# SH4_-_GIMBDRIVE_CONTROLS.net
KiCad netlist of a schematic drawn in Altium Designer
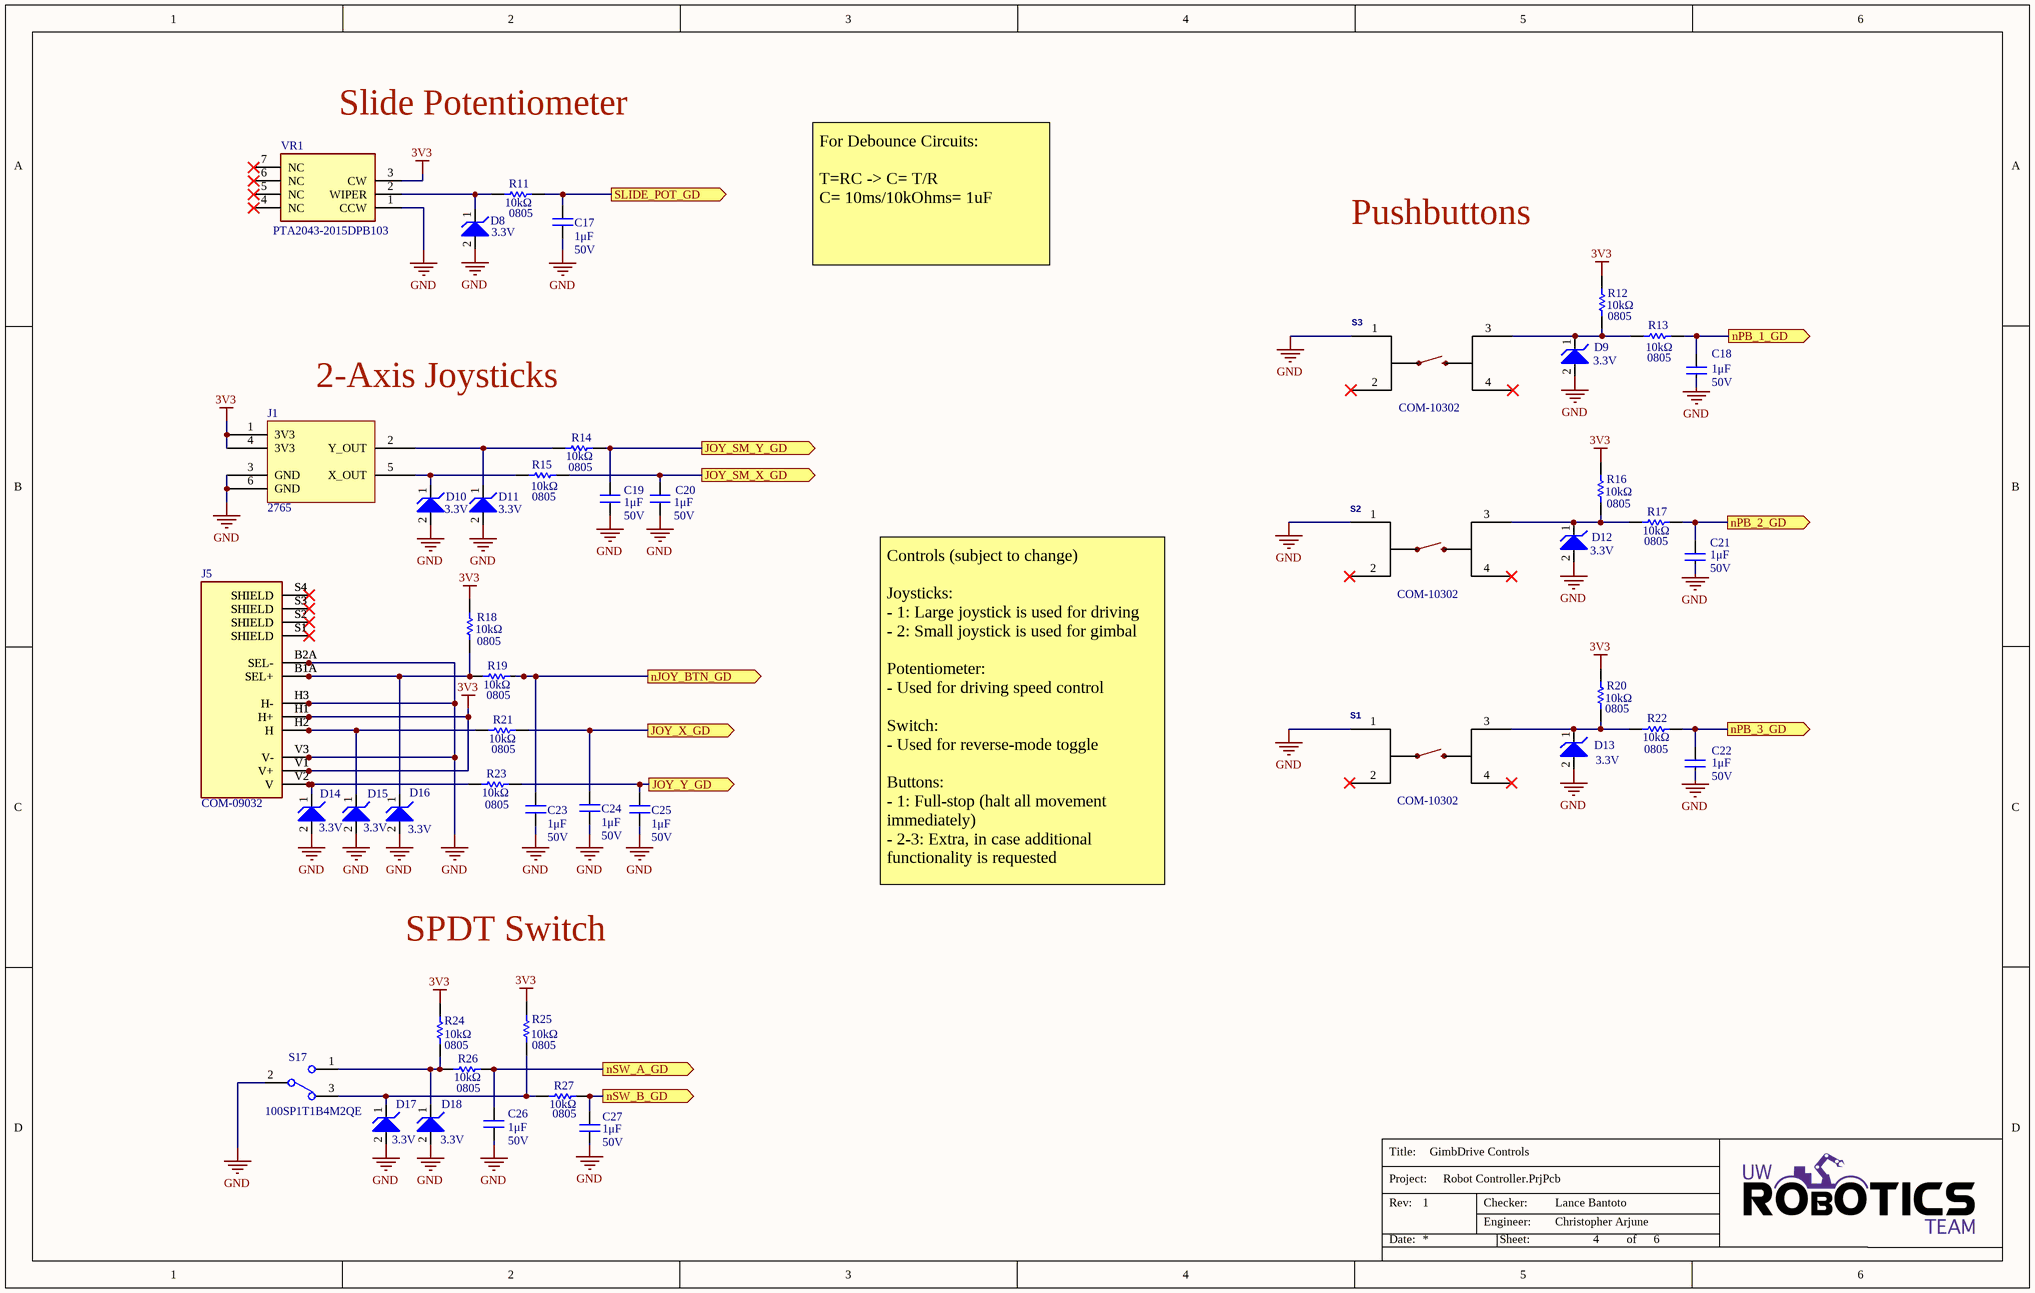
[diagram p0: SH4 - GIMBDRIVE CONTROLS.SchDoc]

(export (version "E")
  (design (tool "Eeschema 10.0.6"))
  (components
    (comp (ref "C17")
      (value "1μF")
      (footprint "CAP2012")
      (description "CAP CER 1UF 50V X7R 0805")
      (fields
        (field (name "VOLTAGE RATING") "50V")
        (field (name "LCSC PART #") "C28323")
        (field (name "Comment") "CAP_1uF_50V_0805")
      )
      (libsource (lib "UWRT_Schematic_Library_2020") (part "CAP_1uF_50V_0805"))
    )
    (comp (ref "C18")
      (value "1μF")
      (footprint "CAP2012")
      (description "CAP CER 1UF 50V X7R 0805")
      (fields
        (field (name "VOLTAGE RATING") "50V")
        (field (name "LCSC PART #") "C28323")
        (field (name "Comment") "CAP_1uF_50V_0805")
      )
      (libsource (lib "UWRT_Schematic_Library_2020") (part "CAP_1uF_50V_0805"))
    )
    (comp (ref "C19")
      (value "1μF")
      (footprint "CAP2012")
      (description "CAP CER 1UF 50V X7R 0805")
      (fields
        (field (name "VOLTAGE RATING") "50V")
        (field (name "LCSC PART #") "C28323")
        (field (name "Comment") "CAP_1uF_50V_0805")
      )
      (libsource (lib "UWRT_Schematic_Library_2020") (part "CAP_1uF_50V_0805"))
    )
    (comp (ref "C20")
      (value "1μF")
      (footprint "CAP2012")
      (description "CAP CER 1UF 50V X7R 0805")
      (fields
        (field (name "VOLTAGE RATING") "50V")
        (field (name "LCSC PART #") "C28323")
        (field (name "Comment") "CAP_1uF_50V_0805")
      )
      (libsource (lib "UWRT_Schematic_Library_2020") (part "CAP_1uF_50V_0805"))
    )
    (comp (ref "C21")
      (value "1μF")
      (footprint "CAP2012")
      (description "CAP CER 1UF 50V X7R 0805")
      (fields
        (field (name "VOLTAGE RATING") "50V")
        (field (name "LCSC PART #") "C28323")
        (field (name "Comment") "CAP_1uF_50V_0805")
      )
      (libsource (lib "UWRT_Schematic_Library_2020") (part "CAP_1uF_50V_0805"))
    )
    (comp (ref "C22")
      (value "1μF")
      (footprint "CAP2012")
      (description "CAP CER 1UF 50V X7R 0805")
      (fields
        (field (name "VOLTAGE RATING") "50V")
        (field (name "LCSC PART #") "C28323")
        (field (name "Comment") "CAP_1uF_50V_0805")
      )
      (libsource (lib "UWRT_Schematic_Library_2020") (part "CAP_1uF_50V_0805"))
    )
    (comp (ref "C23")
      (value "1μF")
      (footprint "CAP2012")
      (description "CAP CER 1UF 50V X7R 0805")
      (fields
        (field (name "VOLTAGE RATING") "50V")
        (field (name "LCSC PART #") "C28323")
        (field (name "Comment") "CAP_1uF_50V_0805")
      )
      (libsource (lib "UWRT_Schematic_Library_2020") (part "CAP_1uF_50V_0805"))
    )
    (comp (ref "C24")
      (value "1μF")
      (footprint "CAP2012")
      (description "CAP CER 1UF 50V X7R 0805")
      (fields
        (field (name "VOLTAGE RATING") "50V")
        (field (name "LCSC PART #") "C28323")
        (field (name "Comment") "CAP_1uF_50V_0805")
      )
      (libsource (lib "UWRT_Schematic_Library_2020") (part "CAP_1uF_50V_0805"))
    )
    (comp (ref "C25")
      (value "1μF")
      (footprint "CAP2012")
      (description "CAP CER 1UF 50V X7R 0805")
      (fields
        (field (name "VOLTAGE RATING") "50V")
        (field (name "LCSC PART #") "C28323")
        (field (name "Comment") "CAP_1uF_50V_0805")
      )
      (libsource (lib "UWRT_Schematic_Library_2020") (part "CAP_1uF_50V_0805"))
    )
    (comp (ref "C26")
      (value "1μF")
      (footprint "CAP2012")
      (description "CAP CER 1UF 50V X7R 0805")
      (fields
        (field (name "VOLTAGE RATING") "50V")
        (field (name "LCSC PART #") "C28323")
        (field (name "Comment") "CAP_1uF_50V_0805")
      )
      (libsource (lib "UWRT_Schematic_Library_2020") (part "CAP_1uF_50V_0805"))
    )
    (comp (ref "C27")
      (value "1μF")
      (footprint "CAP2012")
      (description "CAP CER 1UF 50V X7R 0805")
      (fields
        (field (name "VOLTAGE RATING") "50V")
        (field (name "LCSC PART #") "C28323")
        (field (name "Comment") "CAP_1uF_50V_0805")
      )
      (libsource (lib "UWRT_Schematic_Library_2020") (part "CAP_1uF_50V_0805"))
    )
    (comp (ref "D8")
      (value "TVS_DIODE_UNIDIR_3.3V")
      (description "TVS DIODE 3.3V 14.1V SOD523")
      (fields (field (name "LCSC PART #") "C61148") (field (name "VOLTAGE - REVERSE STANDOFF (TYP)") "3.3V"))
      (libsource (lib "UWRT_Schematic_Library_2020") (part "TVS_DIODE_UNIDIR_3.3V"))
    )
    (comp (ref "D9")
      (value "TVS_DIODE_UNIDIR_3.3V")
      (description "TVS DIODE 3.3V 14.1V SOD523")
      (fields (field (name "LCSC PART #") "C61148") (field (name "VOLTAGE - REVERSE STANDOFF (TYP)") "3.3V"))
      (libsource (lib "UWRT_Schematic_Library_2020") (part "TVS_DIODE_UNIDIR_3.3V"))
    )
    (comp (ref "D10")
      (value "TVS_DIODE_UNIDIR_3.3V")
      (description "TVS DIODE 3.3V 14.1V SOD523")
      (fields (field (name "LCSC PART #") "C61148") (field (name "VOLTAGE - REVERSE STANDOFF (TYP)") "3.3V"))
      (libsource (lib "UWRT_Schematic_Library_2020") (part "TVS_DIODE_UNIDIR_3.3V"))
    )
    (comp (ref "D11")
      (value "TVS_DIODE_UNIDIR_3.3V")
      (description "TVS DIODE 3.3V 14.1V SOD523")
      (fields (field (name "LCSC PART #") "C61148") (field (name "VOLTAGE - REVERSE STANDOFF (TYP)") "3.3V"))
      (libsource (lib "UWRT_Schematic_Library_2020") (part "TVS_DIODE_UNIDIR_3.3V"))
    )
    (comp (ref "D12")
      (value "TVS_DIODE_UNIDIR_3.3V")
      (description "TVS DIODE 3.3V 14.1V SOD523")
      (fields (field (name "LCSC PART #") "C61148") (field (name "VOLTAGE - REVERSE STANDOFF (TYP)") "3.3V"))
      (libsource (lib "UWRT_Schematic_Library_2020") (part "TVS_DIODE_UNIDIR_3.3V"))
    )
    (comp (ref "D13")
      (value "TVS_DIODE_UNIDIR_3.3V")
      (description "TVS DIODE 3.3V 14.1V SOD523")
      (fields (field (name "LCSC PART #") "C61148") (field (name "VOLTAGE - REVERSE STANDOFF (TYP)") "3.3V"))
      (libsource (lib "UWRT_Schematic_Library_2020") (part "TVS_DIODE_UNIDIR_3.3V"))
    )
    (comp (ref "D14")
      (value "TVS_DIODE_UNIDIR_3.3V")
      (description "TVS DIODE 3.3V 14.1V SOD523")
      (fields (field (name "LCSC PART #") "C61148") (field (name "VOLTAGE - REVERSE STANDOFF (TYP)") "3.3V"))
      (libsource (lib "UWRT_Schematic_Library_2020") (part "TVS_DIODE_UNIDIR_3.3V"))
    )
    (comp (ref "D15")
      (value "TVS_DIODE_UNIDIR_3.3V")
      (description "TVS DIODE 3.3V 14.1V SOD523")
      (fields (field (name "LCSC PART #") "C61148") (field (name "VOLTAGE - REVERSE STANDOFF (TYP)") "3.3V"))
      (libsource (lib "UWRT_Schematic_Library_2020") (part "TVS_DIODE_UNIDIR_3.3V"))
    )
    (comp (ref "D16")
      (value "TVS_DIODE_UNIDIR_3.3V")
      (description "TVS DIODE 3.3V 14.1V SOD523")
      (fields (field (name "LCSC PART #") "C61148") (field (name "VOLTAGE - REVERSE STANDOFF (TYP)") "3.3V"))
      (libsource (lib "UWRT_Schematic_Library_2020") (part "TVS_DIODE_UNIDIR_3.3V"))
    )
    (comp (ref "D17")
      (value "TVS_DIODE_UNIDIR_3.3V")
      (description "TVS DIODE 3.3V 14.1V SOD523")
      (fields (field (name "LCSC PART #") "C61148") (field (name "VOLTAGE - REVERSE STANDOFF (TYP)") "3.3V"))
      (libsource (lib "UWRT_Schematic_Library_2020") (part "TVS_DIODE_UNIDIR_3.3V"))
    )
    (comp (ref "D18")
      (value "TVS_DIODE_UNIDIR_3.3V")
      (description "TVS DIODE 3.3V 14.1V SOD523")
      (fields (field (name "LCSC PART #") "C61148") (field (name "VOLTAGE - REVERSE STANDOFF (TYP)") "3.3V"))
      (libsource (lib "UWRT_Schematic_Library_2020") (part "TVS_DIODE_UNIDIR_3.3V"))
    )
    (comp (ref "J1")
      (value "2_AXIS_JOYSTICK_SMALL")
      (footprint "2_AXIS_JOYSTICK_SMALL")
      (description "JOYSTICK 10K OHM 2 AXIS TH")
      (fields (field (name "MANUFACTURER PART NUMBER 1") "2765"))
      (libsource (lib "UWRT_Schematic_Library_2020") (part "2_AXIS_JOYSTICK_SMALL"))
    )
    (comp (ref "J5")
      (value "2_AXIS_JOYSTICK")
      (footprint "2_AXIS_JOYSTICK")
      (description "JOYSTICK 10K OHM 2 AXIS TH")
      (fields (field (name "MANUFACTURER PART NUMBER 1") "COM-09032"))
      (libsource (lib "UWRT_Schematic_Library_2020") (part "2_AXIS_JOYSTICK"))
    )
    (comp (ref "R11")
      (value "10kΩ")
      (footprint "RESC0805")
      (description "RES 10K OHM 5% 1/8W 0805")
      (fields
        (field (name "LCSC PART #") "C17414")
        (field (name "PACKAGE/FOOTPRINT") "0805")
        (field (name "Comment") "RES_10kΩ_0805_5%")
      )
      (libsource (lib "UWRT_Schematic_Library_2020") (part "RES_10kΩ_0805_5%"))
    )
    (comp (ref "R12")
      (value "10kΩ")
      (footprint "RESC0805")
      (description "RES 10K OHM 5% 1/8W 0805")
      (fields
        (field (name "LCSC PART #") "C17414")
        (field (name "PACKAGE/FOOTPRINT") "0805")
        (field (name "Comment") "RES_10kΩ_0805_5%")
      )
      (libsource (lib "UWRT_Schematic_Library_2020") (part "RES_10kΩ_0805_5%"))
    )
    (comp (ref "R13")
      (value "10kΩ")
      (footprint "RESC0805")
      (description "RES 10K OHM 5% 1/8W 0805")
      (fields
        (field (name "LCSC PART #") "C17414")
        (field (name "PACKAGE/FOOTPRINT") "0805")
        (field (name "Comment") "RES_10kΩ_0805_5%")
      )
      (libsource (lib "UWRT_Schematic_Library_2020") (part "RES_10kΩ_0805_5%"))
    )
    (comp (ref "R14")
      (value "10kΩ")
      (footprint "RESC0805")
      (description "RES 10K OHM 5% 1/8W 0805")
      (fields
        (field (name "LCSC PART #") "C17414")
        (field (name "PACKAGE/FOOTPRINT") "0805")
        (field (name "Comment") "RES_10kΩ_0805_5%")
      )
      (libsource (lib "UWRT_Schematic_Library_2020") (part "RES_10kΩ_0805_5%"))
    )
    (comp (ref "R15")
      (value "10kΩ")
      (footprint "RESC0805")
      (description "RES 10K OHM 5% 1/8W 0805")
      (fields
        (field (name "LCSC PART #") "C17414")
        (field (name "PACKAGE/FOOTPRINT") "0805")
        (field (name "Comment") "RES_10kΩ_0805_5%")
      )
      (libsource (lib "UWRT_Schematic_Library_2020") (part "RES_10kΩ_0805_5%"))
    )
    (comp (ref "R16")
      (value "10kΩ")
      (footprint "RESC0805")
      (description "RES 10K OHM 5% 1/8W 0805")
      (fields
        (field (name "LCSC PART #") "C17414")
        (field (name "PACKAGE/FOOTPRINT") "0805")
        (field (name "Comment") "RES_10kΩ_0805_5%")
      )
      (libsource (lib "UWRT_Schematic_Library_2020") (part "RES_10kΩ_0805_5%"))
    )
    (comp (ref "R17")
      (value "10kΩ")
      (footprint "RESC0805")
      (description "RES 10K OHM 5% 1/8W 0805")
      (fields
        (field (name "LCSC PART #") "C17414")
        (field (name "PACKAGE/FOOTPRINT") "0805")
        (field (name "Comment") "RES_10kΩ_0805_5%")
      )
      (libsource (lib "UWRT_Schematic_Library_2020") (part "RES_10kΩ_0805_5%"))
    )
    (comp (ref "R18")
      (value "10kΩ")
      (footprint "RESC0805")
      (description "RES 10K OHM 5% 1/8W 0805")
      (fields
        (field (name "LCSC PART #") "C17414")
        (field (name "PACKAGE/FOOTPRINT") "0805")
        (field (name "Comment") "RES_10kΩ_0805_5%")
      )
      (libsource (lib "UWRT_Schematic_Library_2020") (part "RES_10kΩ_0805_5%"))
    )
    (comp (ref "R19")
      (value "10kΩ")
      (footprint "RESC0805")
      (description "RES 10K OHM 5% 1/8W 0805")
      (fields
        (field (name "LCSC PART #") "C17414")
        (field (name "PACKAGE/FOOTPRINT") "0805")
        (field (name "Comment") "RES_10kΩ_0805_5%")
      )
      (libsource (lib "UWRT_Schematic_Library_2020") (part "RES_10kΩ_0805_5%"))
    )
    (comp (ref "R20")
      (value "10kΩ")
      (footprint "RESC0805")
      (description "RES 10K OHM 5% 1/8W 0805")
      (fields
        (field (name "LCSC PART #") "C17414")
        (field (name "PACKAGE/FOOTPRINT") "0805")
        (field (name "Comment") "RES_10kΩ_0805_5%")
      )
      (libsource (lib "UWRT_Schematic_Library_2020") (part "RES_10kΩ_0805_5%"))
    )
    (comp (ref "R21")
      (value "10kΩ")
      (footprint "RESC0805")
      (description "RES 10K OHM 5% 1/8W 0805")
      (fields
        (field (name "LCSC PART #") "C17414")
        (field (name "PACKAGE/FOOTPRINT") "0805")
        (field (name "Comment") "RES_10kΩ_0805_5%")
      )
      (libsource (lib "UWRT_Schematic_Library_2020") (part "RES_10kΩ_0805_5%"))
    )
    (comp (ref "R22")
      (value "10kΩ")
      (footprint "RESC0805")
      (description "RES 10K OHM 5% 1/8W 0805")
      (fields
        (field (name "LCSC PART #") "C17414")
        (field (name "PACKAGE/FOOTPRINT") "0805")
        (field (name "Comment") "RES_10kΩ_0805_5%")
      )
      (libsource (lib "UWRT_Schematic_Library_2020") (part "RES_10kΩ_0805_5%"))
    )
    (comp (ref "R23")
      (value "10kΩ")
      (footprint "RESC0805")
      (description "RES 10K OHM 5% 1/8W 0805")
      (fields
        (field (name "LCSC PART #") "C17414")
        (field (name "PACKAGE/FOOTPRINT") "0805")
        (field (name "Comment") "RES_10kΩ_0805_5%")
      )
      (libsource (lib "UWRT_Schematic_Library_2020") (part "RES_10kΩ_0805_5%"))
    )
    (comp (ref "R24")
      (value "10kΩ")
      (footprint "RESC0805")
      (description "RES 10K OHM 5% 1/8W 0805")
      (fields
        (field (name "LCSC PART #") "C17414")
        (field (name "PACKAGE/FOOTPRINT") "0805")
        (field (name "Comment") "RES_10kΩ_0805_5%")
      )
      (libsource (lib "UWRT_Schematic_Library_2020") (part "RES_10kΩ_0805_5%"))
    )
    (comp (ref "R25")
      (value "10kΩ")
      (footprint "RESC0805")
      (description "RES 10K OHM 5% 1/8W 0805")
      (fields
        (field (name "LCSC PART #") "C17414")
        (field (name "PACKAGE/FOOTPRINT") "0805")
        (field (name "Comment") "RES_10kΩ_0805_5%")
      )
      (libsource (lib "UWRT_Schematic_Library_2020") (part "RES_10kΩ_0805_5%"))
    )
    (comp (ref "R26")
      (value "10kΩ")
      (footprint "RESC0805")
      (description "RES 10K OHM 5% 1/8W 0805")
      (fields
        (field (name "LCSC PART #") "C17414")
        (field (name "PACKAGE/FOOTPRINT") "0805")
        (field (name "Comment") "RES_10kΩ_0805_5%")
      )
      (libsource (lib "UWRT_Schematic_Library_2020") (part "RES_10kΩ_0805_5%"))
    )
    (comp (ref "R27")
      (value "10kΩ")
      (footprint "RESC0805")
      (description "RES 10K OHM 5% 1/8W 0805")
      (fields
        (field (name "LCSC PART #") "C17414")
        (field (name "PACKAGE/FOOTPRINT") "0805")
        (field (name "Comment") "RES_10kΩ_0805_5%")
      )
      (libsource (lib "UWRT_Schematic_Library_2020") (part "RES_10kΩ_0805_5%"))
    )
    (comp (ref "S1")
      (value "SW_MOMENTARY_PUSHBUTTON")
      (footprint "TACTILE_SWITCH_PTH_12MM")
      (description "TACTILE MOMENTARY PUSHBUTTON SPST")
      (fields (field (name "MANUFACTURER PART NUMBER 1") "COM-10302"))
      (libsource (lib "UWRT_Schematic_Library_2020") (part "SW_MOMENTARY_PUSHBUTTON"))
    )
    (comp (ref "S2")
      (value "SW_MOMENTARY_PUSHBUTTON")
      (footprint "TACTILE_SWITCH_PTH_12MM")
      (description "TACTILE MOMENTARY PUSHBUTTON SPST")
      (fields (field (name "MANUFACTURER PART NUMBER 1") "COM-10302"))
      (libsource (lib "UWRT_Schematic_Library_2020") (part "SW_MOMENTARY_PUSHBUTTON"))
    )
    (comp (ref "S3")
      (value "SW_MOMENTARY_PUSHBUTTON")
      (footprint "TACTILE_SWITCH_PTH_12MM")
      (description "TACTILE MOMENTARY PUSHBUTTON SPST")
      (fields (field (name "MANUFACTURER PART NUMBER 1") "COM-10302"))
      (libsource (lib "UWRT_Schematic_Library_2020") (part "SW_MOMENTARY_PUSHBUTTON"))
    )
    (comp (ref "S17")
      (value "SW_SPDT")
      (footprint "100SP1T1B4M2QE")
      (description "SWITCH TOGGLE SPDT 5A 120V")
      (fields (field (name "MANUFACTURER PART NUMBER 1") "100SP1T1B4M2QE"))
      (libsource (lib "UWRT_Schematic_Library_2020") (part "SW_SPDT"))
    )
    (comp (ref "VR1")
      (value "POT_10K_SLIDE")
      (footprint "PTA20432015CPB103")
      (description "SLIDE POT 10K OHM 0.1W TOP 20MM")
      (fields (field (name "MANUFACTURER PART NUMBER 1") "PTA2043-2015DPB103"))
      (libsource (lib "UWRT_Schematic_Library_2020") (part "POT_10K_SLIDE"))
    )
  )
  (nets
    (net (code "1") (name "/JOY_SM_X_GD") (class "Default")
      (node (ref "C20") (pin "2") (pinfunction "2_2") (pintype "passive"))
      (node (ref "R15") (pin "2") (pinfunction "2_2") (pintype "passive"))
    )
    (net (code "2") (name "/JOY_SM_Y_GD") (class "Default")
      (node (ref "C19") (pin "2") (pinfunction "2_2") (pintype "passive"))
      (node (ref "R14") (pin "2") (pinfunction "2_2") (pintype "passive"))
    )
    (net (code "3") (name "/JOY_X_GD") (class "Default")
      (node (ref "C24") (pin "2") (pinfunction "2_2") (pintype "passive"))
      (node (ref "R21") (pin "2") (pinfunction "2_2") (pintype "passive"))
    )
    (net (code "4") (name "/JOY_Y_GD") (class "Default")
      (node (ref "C25") (pin "2") (pinfunction "2_2") (pintype "passive"))
      (node (ref "R23") (pin "2") (pinfunction "2_2") (pintype "passive"))
    )
    (net (code "5") (name "/SLIDE_POT_GD") (class "Default")
      (node (ref "C17") (pin "2") (pinfunction "2_2") (pintype "passive"))
      (node (ref "R11") (pin "2") (pinfunction "2_2") (pintype "passive"))
    )
    (net (code "6") (name "/nJOY_BTN_GD") (class "Default")
      (node (ref "C23") (pin "2") (pinfunction "2_2") (pintype "passive"))
      (node (ref "R19") (pin "2") (pinfunction "2_2") (pintype "passive"))
    )
    (net (code "7") (name "/nPB_1_GD") (class "Default")
      (node (ref "C18") (pin "2") (pinfunction "2_2") (pintype "passive"))
      (node (ref "R13") (pin "2") (pinfunction "2_2") (pintype "passive"))
    )
    (net (code "8") (name "/nPB_2_GD") (class "Default")
      (node (ref "C21") (pin "2") (pinfunction "2_2") (pintype "passive"))
      (node (ref "R17") (pin "2") (pinfunction "2_2") (pintype "passive"))
    )
    (net (code "9") (name "/nPB_3_GD") (class "Default")
      (node (ref "C22") (pin "2") (pinfunction "2_2") (pintype "passive"))
      (node (ref "R22") (pin "2") (pinfunction "2_2") (pintype "passive"))
    )
    (net (code "10") (name "/nSW_A_GD") (class "Default")
      (node (ref "C26") (pin "2") (pinfunction "2_2") (pintype "passive"))
      (node (ref "R26") (pin "2") (pinfunction "2_2") (pintype "passive"))
    )
    (net (code "11") (name "/nSW_B_GD") (class "Default")
      (node (ref "C27") (pin "2") (pinfunction "2_2") (pintype "passive"))
      (node (ref "R27") (pin "2") (pinfunction "2_2") (pintype "passive"))
    )
    (net (code "12") (name "3V3") (class "Default")
      (node (ref "J1") (pin "1") (pinfunction "3V3_1") (pintype "passive"))
      (node (ref "J1") (pin "4") (pinfunction "3V3_4") (pintype "passive"))
      (node (ref "J5") (pin "H1") (pinfunction "H+_H1") (pintype "passive"))
      (node (ref "J5") (pin "V1") (pinfunction "V+_V1") (pintype "passive"))
      (node (ref "R12") (pin "1") (pinfunction "1_1") (pintype "passive"))
      (node (ref "R16") (pin "1") (pinfunction "1_1") (pintype "passive"))
      (node (ref "R18") (pin "1") (pinfunction "1_1") (pintype "passive"))
      (node (ref "R20") (pin "1") (pinfunction "1_1") (pintype "passive"))
      (node (ref "R24") (pin "1") (pinfunction "1_1") (pintype "passive"))
      (node (ref "R25") (pin "1") (pinfunction "1_1") (pintype "passive"))
      (node (ref "VR1") (pin "3") (pinfunction "CW_3") (pintype "passive"))
    )
    (net (code "13") (name "GND") (class "Default")
      (node (ref "C17") (pin "1") (pinfunction "1_1") (pintype "passive"))
      (node (ref "C18") (pin "1") (pinfunction "1_1") (pintype "passive"))
      (node (ref "C19") (pin "1") (pinfunction "1_1") (pintype "passive"))
      (node (ref "C20") (pin "1") (pinfunction "1_1") (pintype "passive"))
      (node (ref "C21") (pin "1") (pinfunction "1_1") (pintype "passive"))
      (node (ref "C22") (pin "1") (pinfunction "1_1") (pintype "passive"))
      (node (ref "C23") (pin "1") (pinfunction "1_1") (pintype "passive"))
      (node (ref "C24") (pin "1") (pinfunction "1_1") (pintype "passive"))
      (node (ref "C25") (pin "1") (pinfunction "1_1") (pintype "passive"))
      (node (ref "C26") (pin "1") (pinfunction "1_1") (pintype "passive"))
      (node (ref "C27") (pin "1") (pinfunction "1_1") (pintype "passive"))
      (node (ref "D10") (pin "2") (pinfunction "2_2") (pintype "passive"))
      (node (ref "D11") (pin "2") (pinfunction "2_2") (pintype "passive"))
      (node (ref "D12") (pin "2") (pinfunction "2_2") (pintype "passive"))
      (node (ref "D13") (pin "2") (pinfunction "2_2") (pintype "passive"))
      (node (ref "D14") (pin "2") (pinfunction "2_2") (pintype "passive"))
      (node (ref "D15") (pin "2") (pinfunction "2_2") (pintype "passive"))
      (node (ref "D16") (pin "2") (pinfunction "2_2") (pintype "passive"))
      (node (ref "D17") (pin "2") (pinfunction "2_2") (pintype "passive"))
      (node (ref "D18") (pin "2") (pinfunction "2_2") (pintype "passive"))
      (node (ref "D8") (pin "2") (pinfunction "2_2") (pintype "passive"))
      (node (ref "D9") (pin "2") (pinfunction "2_2") (pintype "passive"))
      (node (ref "J1") (pin "3") (pinfunction "GND_3") (pintype "passive"))
      (node (ref "J1") (pin "6") (pinfunction "GND_6") (pintype "passive"))
      (node (ref "J5") (pin "B2A") (pinfunction "SEL-_B2A") (pintype "passive"))
      (node (ref "J5") (pin "H3") (pinfunction "H-_H3") (pintype "passive"))
      (node (ref "J5") (pin "V3") (pinfunction "V-_V3") (pintype "passive"))
      (node (ref "S1") (pin "1") (pinfunction "1_1") (pintype "passive"))
      (node (ref "S17") (pin "2") (pinfunction "2_2") (pintype "passive"))
      (node (ref "S2") (pin "1") (pinfunction "1_1") (pintype "passive"))
      (node (ref "S3") (pin "1") (pinfunction "1_1") (pintype "passive"))
      (node (ref "VR1") (pin "1") (pinfunction "CCW_1") (pintype "passive"))
    )
    (net (code "14") (name "Net-(D9-Pad1)") (class "Default")
      (node (ref "D9") (pin "1") (pinfunction "1_1") (pintype "passive"))
      (node (ref "R12") (pin "2") (pinfunction "2_2") (pintype "passive"))
      (node (ref "R13") (pin "1") (pinfunction "1_1") (pintype "passive"))
      (node (ref "S3") (pin "3") (pinfunction "3_3") (pintype "passive"))
    )
    (net (code "15") (name "Net-(D12-Pad1)") (class "Default")
      (node (ref "D12") (pin "1") (pinfunction "1_1") (pintype "passive"))
      (node (ref "R16") (pin "2") (pinfunction "2_2") (pintype "passive"))
      (node (ref "R17") (pin "1") (pinfunction "1_1") (pintype "passive"))
      (node (ref "S2") (pin "3") (pinfunction "3_3") (pintype "passive"))
    )
    (net (code "16") (name "Net-(D13-Pad1)") (class "Default")
      (node (ref "D13") (pin "1") (pinfunction "1_1") (pintype "passive"))
      (node (ref "R20") (pin "2") (pinfunction "2_2") (pintype "passive"))
      (node (ref "R22") (pin "1") (pinfunction "1_1") (pintype "passive"))
      (node (ref "S1") (pin "3") (pinfunction "3_3") (pintype "passive"))
    )
    (net (code "17") (name "Net-(D17-Pad1)") (class "Default")
      (node (ref "D17") (pin "1") (pinfunction "1_1") (pintype "passive"))
      (node (ref "R25") (pin "2") (pinfunction "2_2") (pintype "passive"))
      (node (ref "R27") (pin "1") (pinfunction "1_1") (pintype "passive"))
      (node (ref "S17") (pin "3") (pinfunction "3_3") (pintype "passive"))
    )
    (net (code "18") (name "Net-(D18-Pad1)") (class "Default")
      (node (ref "D18") (pin "1") (pinfunction "1_1") (pintype "passive"))
      (node (ref "R24") (pin "2") (pinfunction "2_2") (pintype "passive"))
      (node (ref "R26") (pin "1") (pinfunction "1_1") (pintype "passive"))
      (node (ref "S17") (pin "1") (pinfunction "1_1") (pintype "passive"))
    )
    (net (code "19") (name "Net-(J1-X_OUT)") (class "Default")
      (node (ref "D10") (pin "1") (pinfunction "1_1") (pintype "passive"))
      (node (ref "J1") (pin "5") (pinfunction "X_OUT_5") (pintype "passive"))
      (node (ref "R15") (pin "1") (pinfunction "1_1") (pintype "passive"))
    )
    (net (code "20") (name "Net-(J1-Y_OUT)") (class "Default")
      (node (ref "D11") (pin "1") (pinfunction "1_1") (pintype "passive"))
      (node (ref "J1") (pin "2") (pinfunction "Y_OUT_2") (pintype "passive"))
      (node (ref "R14") (pin "1") (pinfunction "1_1") (pintype "passive"))
    )
    (net (code "21") (name "Net-(J5-H)") (class "Default")
      (node (ref "D15") (pin "1") (pinfunction "1_1") (pintype "passive"))
      (node (ref "J5") (pin "H2") (pinfunction "H_H2") (pintype "passive"))
      (node (ref "R21") (pin "1") (pinfunction "1_1") (pintype "passive"))
    )
    (net (code "22") (name "Net-(J5-SEL+)") (class "Default")
      (node (ref "D16") (pin "1") (pinfunction "1_1") (pintype "passive"))
      (node (ref "J5") (pin "B1A") (pinfunction "SEL+_B1A") (pintype "passive"))
      (node (ref "R18") (pin "2") (pinfunction "2_2") (pintype "passive"))
      (node (ref "R19") (pin "1") (pinfunction "1_1") (pintype "passive"))
    )
    (net (code "23") (name "Net-(J5-V)") (class "Default")
      (node (ref "D14") (pin "1") (pinfunction "1_1") (pintype "passive"))
      (node (ref "J5") (pin "V2") (pinfunction "V_V2") (pintype "passive"))
      (node (ref "R23") (pin "1") (pinfunction "1_1") (pintype "passive"))
    )
    (net (code "24") (name "Net-(VR1-WIPER)") (class "Default")
      (node (ref "D8") (pin "1") (pinfunction "1_1") (pintype "passive"))
      (node (ref "R11") (pin "1") (pinfunction "1_1") (pintype "passive"))
      (node (ref "VR1") (pin "2") (pinfunction "WIPER_2") (pintype "passive"))
    )
    (net (code "25") (name "unconnected-(J5-SHIELD-PadS1)") (class "Default")
      (node (ref "J5") (pin "S1") (pinfunction "SHIELD_S1") (pintype "passive+no_connect"))
    )
    (net (code "26") (name "unconnected-(J5-SHIELD-PadS2)") (class "Default")
      (node (ref "J5") (pin "S2") (pinfunction "SHIELD_S2") (pintype "passive+no_connect"))
    )
    (net (code "27") (name "unconnected-(J5-SHIELD-PadS3)") (class "Default")
      (node (ref "J5") (pin "S3") (pinfunction "SHIELD_S3") (pintype "passive+no_connect"))
    )
    (net (code "28") (name "unconnected-(J5-SHIELD-PadS4)") (class "Default")
      (node (ref "J5") (pin "S4") (pinfunction "SHIELD_S4") (pintype "passive+no_connect"))
    )
    (net (code "29") (name "unconnected-(S1-Pad2)") (class "Default")
      (node (ref "S1") (pin "2") (pinfunction "2_2") (pintype "passive+no_connect"))
    )
    (net (code "30") (name "unconnected-(S1-Pad4)") (class "Default")
      (node (ref "S1") (pin "4") (pinfunction "4_4") (pintype "passive+no_connect"))
    )
    (net (code "31") (name "unconnected-(S2-Pad2)") (class "Default")
      (node (ref "S2") (pin "2") (pinfunction "2_2") (pintype "passive+no_connect"))
    )
    (net (code "32") (name "unconnected-(S2-Pad4)") (class "Default")
      (node (ref "S2") (pin "4") (pinfunction "4_4") (pintype "passive+no_connect"))
    )
    (net (code "33") (name "unconnected-(S3-Pad2)") (class "Default")
      (node (ref "S3") (pin "2") (pinfunction "2_2") (pintype "passive+no_connect"))
    )
    (net (code "34") (name "unconnected-(S3-Pad4)") (class "Default")
      (node (ref "S3") (pin "4") (pinfunction "4_4") (pintype "passive+no_connect"))
    )
    (net (code "35") (name "unconnected-(VR1-NC-Pad4)") (class "Default")
      (node (ref "VR1") (pin "4") (pinfunction "NC_4") (pintype "passive+no_connect"))
    )
    (net (code "36") (name "unconnected-(VR1-NC-Pad5)") (class "Default")
      (node (ref "VR1") (pin "5") (pinfunction "NC_5") (pintype "passive+no_connect"))
    )
    (net (code "37") (name "unconnected-(VR1-NC-Pad6)") (class "Default")
      (node (ref "VR1") (pin "6") (pinfunction "NC_6") (pintype "passive+no_connect"))
    )
    (net (code "38") (name "unconnected-(VR1-NC-Pad7)") (class "Default")
      (node (ref "VR1") (pin "7") (pinfunction "NC_7") (pintype "passive+no_connect"))
    )
  )
)
